# T_STorM32_motor_v25E.net
KiCad netlist of a schematic drawn in EAGLE
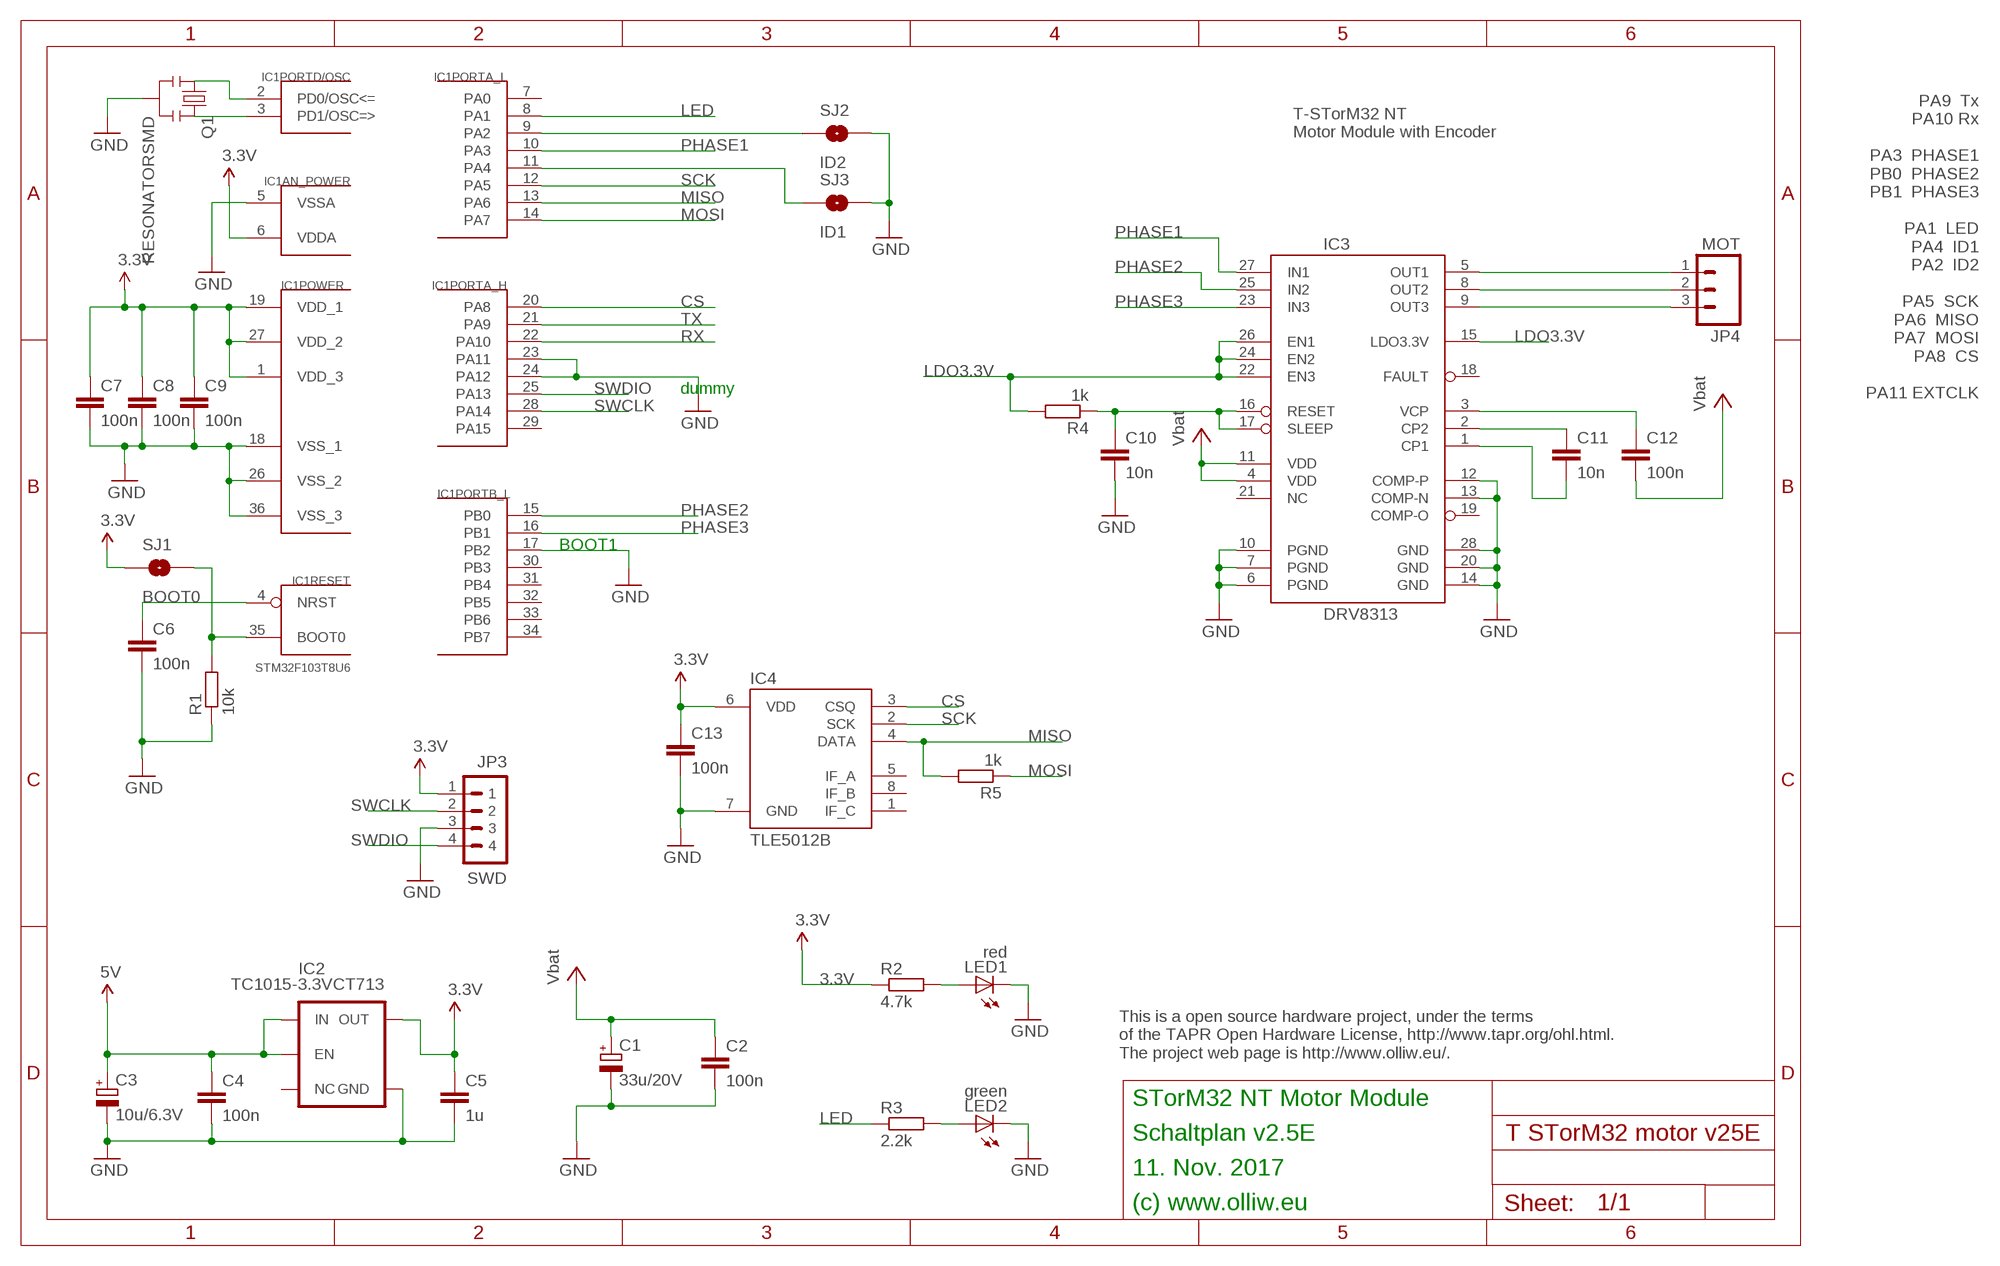
[diagram p0: schematic, sheet 1]

(export (version "E")
  (design (tool "Eeschema 10.0.6"))
  (components
    (comp (ref "C1")
      (value "33u/20V")
      (footprint "eagle-import:SMC_C")
      (libsource (lib "eagle-import") (part "CPOL-EUSMCC"))
    )
    (comp (ref "C2")
      (value "100n")
      (footprint "eagle-import:C0603")
      (libsource (lib "eagle-import") (part "C-EUC0603"))
    )
    (comp (ref "C3")
      (value "10u/6.3V")
      (footprint "eagle-import:SMC_B")
      (libsource (lib "eagle-import") (part "CPOL-EUSMCB"))
    )
    (comp (ref "C4")
      (value "100n")
      (footprint "eagle-import:C0603")
      (libsource (lib "eagle-import") (part "C-EUC0603"))
    )
    (comp (ref "C5")
      (value "1u")
      (footprint "eagle-import:C0603")
      (libsource (lib "eagle-import") (part "C-EUC0603"))
    )
    (comp (ref "C6")
      (value "100n")
      (footprint "eagle-import:C0603")
      (libsource (lib "eagle-import") (part "C-EUC0603"))
    )
    (comp (ref "C7")
      (value "100n")
      (footprint "eagle-import:C0603")
      (libsource (lib "eagle-import") (part "C-EUC0603"))
    )
    (comp (ref "C8")
      (value "100n")
      (footprint "eagle-import:C0603")
      (libsource (lib "eagle-import") (part "C-EUC0603"))
    )
    (comp (ref "C9")
      (value "100n")
      (footprint "eagle-import:C0603")
      (libsource (lib "eagle-import") (part "C-EUC0603"))
    )
    (comp (ref "C10")
      (value "10n")
      (footprint "eagle-import:C0603")
      (libsource (lib "eagle-import") (part "C-EUC0603"))
    )
    (comp (ref "C11")
      (value "10n")
      (footprint "eagle-import:C0603")
      (libsource (lib "eagle-import") (part "C-EUC0603"))
    )
    (comp (ref "C12")
      (value "100n")
      (footprint "eagle-import:C0603")
      (libsource (lib "eagle-import") (part "C-EUC0603"))
    )
    (comp (ref "C13")
      (value "100n")
      (footprint "eagle-import:C0603")
      (libsource (lib "eagle-import") (part "C-EUC0603"))
    )
    (comp (ref "IC1")
      (value "STM32F103T8U6")
      (footprint "eagle-import:VFQFPN36")
      (libsource (lib "eagle-import") (part "STM32F10XTXU6"))
    )
    (comp (ref "IC2")
      (value "TC1015-3.3VCT713")
      (footprint "eagle-import:SOT23-5")
      (libsource (lib "eagle-import") (part "V_REG_TPS76433SOT23-5"))
    )
    (comp (ref "IC3")
      (value "DRV8313")
      (footprint "eagle-import:HTSSOP28")
      (libsource (lib "eagle-import") (part "DRV8313"))
    )
    (comp (ref "IC4")
      (value "TLE5012B")
      (footprint "eagle-import:SO08")
      (libsource (lib "eagle-import") (part "TLE5012B"))
    )
    (comp (ref "JP3")
      (value "SWD")
      (footprint "eagle-import:4X1_1P27_OCT_BILEX")
      (libsource (lib "eagle-import") (part "P4X1_1P27-OCT_BILEX"))
    )
    (comp (ref "JP4")
      (value "MOT")
      (footprint "eagle-import:1X03_NO_SILK")
      (libsource (lib "eagle-import") (part "M031X03_NO_SILK"))
    )
    (comp (ref "LED1")
      (value "red")
      (footprint "eagle-import:CHIPLED_0603")
      (libsource (lib "eagle-import") (part "LEDCHIPLED_0603"))
    )
    (comp (ref "LED2")
      (value "green")
      (footprint "eagle-import:CHIPLED_0603")
      (libsource (lib "eagle-import") (part "LEDCHIPLED_0603"))
    )
    (comp (ref "Q1")
      (value "RESONATORSMD")
      (footprint "eagle-import:RESONATOR-SMD")
      (libsource (lib "eagle-import") (part "RESONATORSMD"))
    )
    (comp (ref "R1")
      (value "10k")
      (footprint "eagle-import:R0603")
      (libsource (lib "eagle-import") (part "R-EU_R0603"))
    )
    (comp (ref "R2")
      (value "4.7k")
      (footprint "eagle-import:R0603")
      (libsource (lib "eagle-import") (part "R-EU_R0603"))
    )
    (comp (ref "R3")
      (value "2.2k")
      (footprint "eagle-import:R0603")
      (libsource (lib "eagle-import") (part "R-EU_R0603"))
    )
    (comp (ref "R4")
      (value "1k")
      (footprint "eagle-import:R0603")
      (libsource (lib "eagle-import") (part "R-EU_R0603"))
    )
    (comp (ref "R5")
      (value "1k")
      (footprint "eagle-import:R0603")
      (libsource (lib "eagle-import") (part "R-EU_R0603"))
    )
    (comp (ref "SJ1")
      (value "BOOT0")
      (footprint "eagle-import:SJ_2S-NO")
      (libsource (lib "eagle-import") (part "SOLDERJUMPERNO"))
    )
    (comp (ref "SJ2")
      (value "ID2")
      (footprint "eagle-import:SJ_2S-NO")
      (libsource (lib "eagle-import") (part "SOLDERJUMPERNO"))
    )
    (comp (ref "SJ3")
      (value "ID1")
      (footprint "eagle-import:SJ_2S-NO")
      (libsource (lib "eagle-import") (part "SOLDERJUMPERNO"))
    )
  )
  (nets
    (net (code "1") (name "/CS") (class "Default")
      (node (ref "IC1") (pin "20") (pinfunction "PA8_20") (pintype "bidirectional"))
      (node (ref "IC4") (pin "3") (pinfunction "CSQ_3") (pintype "input"))
    )
    (net (code "2") (name "/LDO3.3V") (class "Default")
      (node (ref "IC3") (pin "15") (pinfunction "LDO3.3V_15") (pintype "output"))
      (node (ref "IC3") (pin "22") (pinfunction "EN3_22") (pintype "input"))
      (node (ref "IC3") (pin "24") (pinfunction "EN2_24") (pintype "input"))
      (node (ref "IC3") (pin "26") (pinfunction "EN1_26") (pintype "input"))
      (node (ref "R4") (pin "2") (pinfunction "2_2") (pintype "passive"))
    )
    (net (code "3") (name "/LED") (class "Default")
      (node (ref "IC1") (pin "8") (pinfunction "PA1_8") (pintype "bidirectional"))
      (node (ref "R3") (pin "1") (pinfunction "1_1") (pintype "passive"))
    )
    (net (code "4") (name "/MISO") (class "Default")
      (node (ref "IC1") (pin "13") (pinfunction "PA6_13") (pintype "bidirectional"))
      (node (ref "IC4") (pin "4") (pinfunction "DATA_4") (pintype "bidirectional"))
      (node (ref "R5") (pin "2") (pinfunction "2_2") (pintype "passive"))
    )
    (net (code "5") (name "/MOSI") (class "Default")
      (node (ref "IC1") (pin "14") (pinfunction "PA7_14") (pintype "bidirectional"))
      (node (ref "R5") (pin "1") (pinfunction "1_1") (pintype "passive"))
    )
    (net (code "6") (name "/PHASE1") (class "Default")
      (node (ref "IC1") (pin "10") (pinfunction "PA3_10") (pintype "bidirectional"))
      (node (ref "IC3") (pin "27") (pinfunction "IN1_27") (pintype "input"))
    )
    (net (code "7") (name "/PHASE2") (class "Default")
      (node (ref "IC1") (pin "15") (pinfunction "PB0_15") (pintype "bidirectional"))
      (node (ref "IC3") (pin "25") (pinfunction "IN2_25") (pintype "input"))
    )
    (net (code "8") (name "/PHASE3") (class "Default")
      (node (ref "IC1") (pin "16") (pinfunction "PB1_16") (pintype "bidirectional"))
      (node (ref "IC3") (pin "23") (pinfunction "IN3_23") (pintype "input"))
    )
    (net (code "9") (name "/RX") (class "Default")
      (node (ref "IC1") (pin "22") (pinfunction "PA10_22") (pintype "bidirectional"))
    )
    (net (code "10") (name "/SCK") (class "Default")
      (node (ref "IC1") (pin "12") (pinfunction "PA5_12") (pintype "bidirectional"))
      (node (ref "IC4") (pin "2") (pinfunction "SCK_2") (pintype "input"))
    )
    (net (code "11") (name "/SWCLK") (class "Default")
      (node (ref "IC1") (pin "28") (pinfunction "PA14_28") (pintype "bidirectional"))
      (node (ref "JP3") (pin "2") (pinfunction "2_2") (pintype "passive"))
    )
    (net (code "12") (name "/SWDIO") (class "Default")
      (node (ref "IC1") (pin "25") (pinfunction "PA13_25") (pintype "bidirectional"))
      (node (ref "JP3") (pin "4") (pinfunction "4_4") (pintype "passive"))
    )
    (net (code "13") (name "/TX") (class "Default")
      (node (ref "IC1") (pin "21") (pinfunction "PA9_21") (pintype "bidirectional"))
    )
    (net (code "14") (name "3.3V") (class "Default")
      (node (ref "C13") (pin "1") (pinfunction "1_1") (pintype "passive"))
      (node (ref "C5") (pin "1") (pinfunction "1_1") (pintype "passive"))
      (node (ref "C7") (pin "1") (pinfunction "1_1") (pintype "passive"))
      (node (ref "C8") (pin "1") (pinfunction "1_1") (pintype "passive"))
      (node (ref "C9") (pin "1") (pinfunction "1_1") (pintype "passive"))
      (node (ref "IC1") (pin "1") (pinfunction "VDD_3_1") (pintype "power_in"))
      (node (ref "IC1") (pin "19") (pinfunction "VDD_1_19") (pintype "power_in"))
      (node (ref "IC1") (pin "27") (pinfunction "VDD_2_27") (pintype "power_in"))
      (node (ref "IC1") (pin "6") (pinfunction "VDDA_6") (pintype "power_in"))
      (node (ref "IC2") (pin "5") (pinfunction "OUT_5") (pintype "passive"))
      (node (ref "IC4") (pin "6") (pinfunction "VDD_6") (pintype "power_in"))
      (node (ref "JP3") (pin "1") (pinfunction "1_1") (pintype "passive"))
      (node (ref "R2") (pin "1") (pinfunction "1_1") (pintype "passive"))
      (node (ref "SJ1") (pin "1") (pinfunction "1_1") (pintype "passive"))
    )
    (net (code "15") (name "5V") (class "Default")
      (node (ref "C3") (pin "+") (pinfunction "+_+") (pintype "passive"))
      (node (ref "C4") (pin "1") (pinfunction "1_1") (pintype "passive"))
      (node (ref "IC2") (pin "1") (pinfunction "IN_1") (pintype "input"))
      (node (ref "IC2") (pin "3") (pinfunction "EN_3") (pintype "input"))
    )
    (net (code "16") (name "GND") (class "Default")
      (node (ref "C1") (pin "-") (pinfunction "-_-") (pintype "passive"))
      (node (ref "C10") (pin "2") (pinfunction "2_2") (pintype "passive"))
      (node (ref "C13") (pin "2") (pinfunction "2_2") (pintype "passive"))
      (node (ref "C2") (pin "2") (pinfunction "2_2") (pintype "passive"))
      (node (ref "C3") (pin "-") (pinfunction "-_-") (pintype "passive"))
      (node (ref "C4") (pin "2") (pinfunction "2_2") (pintype "passive"))
      (node (ref "C5") (pin "2") (pinfunction "2_2") (pintype "passive"))
      (node (ref "C6") (pin "2") (pinfunction "2_2") (pintype "passive"))
      (node (ref "C7") (pin "2") (pinfunction "2_2") (pintype "passive"))
      (node (ref "C8") (pin "2") (pinfunction "2_2") (pintype "passive"))
      (node (ref "C9") (pin "2") (pinfunction "2_2") (pintype "passive"))
      (node (ref "IC1") (pin "17") (pinfunction "PB2_17") (pintype "bidirectional"))
      (node (ref "IC1") (pin "18") (pinfunction "VSS_1_18") (pintype "power_in"))
      (node (ref "IC1") (pin "23") (pinfunction "PA11_23") (pintype "bidirectional"))
      (node (ref "IC1") (pin "24") (pinfunction "PA12_24") (pintype "bidirectional"))
      (node (ref "IC1") (pin "26") (pinfunction "VSS_2_26") (pintype "power_in"))
      (node (ref "IC1") (pin "36") (pinfunction "VSS_3_36") (pintype "power_in"))
      (node (ref "IC1") (pin "5") (pinfunction "VSSA_5") (pintype "power_in"))
      (node (ref "IC2") (pin "2") (pinfunction "GND_2") (pintype "input"))
      (node (ref "IC3") (pin "10") (pinfunction "PGND_10") (pintype "power_in"))
      (node (ref "IC3") (pin "12") (pinfunction "COMP-P_12") (pintype "input"))
      (node (ref "IC3") (pin "13") (pinfunction "COMP-N_13") (pintype "input"))
      (node (ref "IC3") (pin "14") (pinfunction "GND_14") (pintype "power_in"))
      (node (ref "IC3") (pin "20") (pinfunction "GND_20") (pintype "power_in"))
      (node (ref "IC3") (pin "28") (pinfunction "GND_28") (pintype "power_in"))
      (node (ref "IC3") (pin "6") (pinfunction "PGND_6") (pintype "power_in"))
      (node (ref "IC3") (pin "7") (pinfunction "PGND_7") (pintype "power_in"))
      (node (ref "IC4") (pin "7") (pinfunction "GND_7") (pintype "power_in"))
      (node (ref "JP3") (pin "3") (pinfunction "3_3") (pintype "passive"))
      (node (ref "LED1") (pin "C") (pinfunction "C_C") (pintype "passive"))
      (node (ref "LED2") (pin "C") (pinfunction "C_C") (pintype "passive"))
      (node (ref "Q1") (pin "2") (pinfunction "2_2") (pintype "passive"))
      (node (ref "R1") (pin "1") (pinfunction "1_1") (pintype "passive"))
      (node (ref "SJ2") (pin "2") (pinfunction "2_2") (pintype "passive"))
      (node (ref "SJ3") (pin "2") (pinfunction "2_2") (pintype "passive"))
    )
    (net (code "17") (name "Net-(IC1C-PA2)") (class "Default")
      (node (ref "IC1") (pin "9") (pinfunction "PA2_9") (pintype "bidirectional"))
      (node (ref "SJ2") (pin "1") (pinfunction "1_1") (pintype "passive"))
    )
    (net (code "18") (name "Net-(IC1C-PA4)") (class "Default")
      (node (ref "IC1") (pin "11") (pinfunction "PA4_11") (pintype "bidirectional"))
      (node (ref "SJ3") (pin "1") (pinfunction "1_1") (pintype "passive"))
    )
    (net (code "19") (name "Net-(IC1E-PD0{slash}OSC<=)") (class "Default")
      (node (ref "IC1") (pin "2") (pinfunction "PD0/OSC<=_2") (pintype "bidirectional"))
      (node (ref "Q1") (pin "1") (pinfunction "1_1") (pintype "passive"))
    )
    (net (code "20") (name "Net-(IC1E-PD1{slash}OSC=>)") (class "Default")
      (node (ref "IC1") (pin "3") (pinfunction "PD1/OSC=>_3") (pintype "bidirectional"))
      (node (ref "Q1") (pin "3") (pinfunction "3_3") (pintype "passive"))
    )
    (net (code "21") (name "Net-(IC1G-BOOT0)") (class "Default")
      (node (ref "IC1") (pin "35") (pinfunction "BOOT0_35") (pintype "input"))
      (node (ref "R1") (pin "2") (pinfunction "2_2") (pintype "passive"))
      (node (ref "SJ1") (pin "2") (pinfunction "2_2") (pintype "passive"))
    )
    (net (code "22") (name "Net-(IC1G-NRST)") (class "Default")
      (node (ref "C6") (pin "1") (pinfunction "1_1") (pintype "passive"))
      (node (ref "IC1") (pin "4") (pinfunction "NRST_4") (pintype "input"))
    )
    (net (code "23") (name "Net-(IC3-CP1)") (class "Default")
      (node (ref "C11") (pin "2") (pinfunction "2_2") (pintype "passive"))
      (node (ref "IC3") (pin "1") (pinfunction "CP1_1") (pintype "bidirectional"))
    )
    (net (code "24") (name "Net-(IC3-CP2)") (class "Default")
      (node (ref "C11") (pin "1") (pinfunction "1_1") (pintype "passive"))
      (node (ref "IC3") (pin "2") (pinfunction "CP2_2") (pintype "bidirectional"))
    )
    (net (code "25") (name "Net-(IC3-OUT1)") (class "Default")
      (node (ref "IC3") (pin "5") (pinfunction "OUT1_5") (pintype "output"))
      (node (ref "JP4") (pin "1") (pinfunction "1_1") (pintype "passive"))
    )
    (net (code "26") (name "Net-(IC3-OUT2)") (class "Default")
      (node (ref "IC3") (pin "8") (pinfunction "OUT2_8") (pintype "output"))
      (node (ref "JP4") (pin "2") (pinfunction "2_2") (pintype "passive"))
    )
    (net (code "27") (name "Net-(IC3-OUT3)") (class "Default")
      (node (ref "IC3") (pin "9") (pinfunction "OUT3_9") (pintype "output"))
      (node (ref "JP4") (pin "3") (pinfunction "3_3") (pintype "passive"))
    )
    (net (code "28") (name "Net-(IC3-RESET)") (class "Default")
      (node (ref "C10") (pin "1") (pinfunction "1_1") (pintype "passive"))
      (node (ref "IC3") (pin "16") (pinfunction "RESET_16") (pintype "input"))
      (node (ref "IC3") (pin "17") (pinfunction "SLEEP_17") (pintype "input"))
      (node (ref "R4") (pin "1") (pinfunction "1_1") (pintype "passive"))
    )
    (net (code "29") (name "Net-(IC3-VCP)") (class "Default")
      (node (ref "C12") (pin "1") (pinfunction "1_1") (pintype "passive"))
      (node (ref "IC3") (pin "3") (pinfunction "VCP_3") (pintype "bidirectional"))
    )
    (net (code "30") (name "Net-(LED1-PadA)") (class "Default")
      (node (ref "LED1") (pin "A") (pinfunction "A_A") (pintype "passive"))
      (node (ref "R2") (pin "2") (pinfunction "2_2") (pintype "passive"))
    )
    (net (code "31") (name "Net-(LED2-PadA)") (class "Default")
      (node (ref "LED2") (pin "A") (pinfunction "A_A") (pintype "passive"))
      (node (ref "R3") (pin "2") (pinfunction "2_2") (pintype "passive"))
    )
    (net (code "32") (name "Vbat") (class "Default")
      (node (ref "C1") (pin "+") (pinfunction "+_+") (pintype "passive"))
      (node (ref "C12") (pin "2") (pinfunction "2_2") (pintype "passive"))
      (node (ref "C2") (pin "1") (pinfunction "1_1") (pintype "passive"))
      (node (ref "IC3") (pin "11") (pinfunction "VDD_11") (pintype "power_in"))
      (node (ref "IC3") (pin "4") (pinfunction "VDD_4") (pintype "power_in"))
    )
    (net (code "33") (name "unconnected-(IC1B-PA15-Pad29)") (class "Default")
      (node (ref "IC1") (pin "29") (pinfunction "PA15_29") (pintype "bidirectional"))
    )
    (net (code "34") (name "unconnected-(IC1C-PA0-Pad7)") (class "Default")
      (node (ref "IC1") (pin "7") (pinfunction "PA0_7") (pintype "bidirectional"))
    )
    (net (code "35") (name "unconnected-(IC1D-PB3-Pad30)") (class "Default")
      (node (ref "IC1") (pin "30") (pinfunction "PB3_30") (pintype "bidirectional"))
    )
    (net (code "36") (name "unconnected-(IC1D-PB4-Pad31)") (class "Default")
      (node (ref "IC1") (pin "31") (pinfunction "PB4_31") (pintype "bidirectional"))
    )
    (net (code "37") (name "unconnected-(IC1D-PB5-Pad32)") (class "Default")
      (node (ref "IC1") (pin "32") (pinfunction "PB5_32") (pintype "bidirectional"))
    )
    (net (code "38") (name "unconnected-(IC1D-PB6-Pad33)") (class "Default")
      (node (ref "IC1") (pin "33") (pinfunction "PB6_33") (pintype "bidirectional"))
    )
    (net (code "39") (name "unconnected-(IC1D-PB7-Pad34)") (class "Default")
      (node (ref "IC1") (pin "34") (pinfunction "PB7_34") (pintype "bidirectional"))
    )
    (net (code "40") (name "unconnected-(IC2-NC-Pad4)") (class "Default")
      (node (ref "IC2") (pin "4") (pinfunction "NC_4") (pintype "input"))
    )
    (net (code "41") (name "unconnected-(IC3-COMP-O-Pad19)") (class "Default")
      (node (ref "IC3") (pin "19") (pinfunction "COMP-O_19") (pintype "output"))
    )
    (net (code "42") (name "unconnected-(IC3-FAULT-Pad18)") (class "Default")
      (node (ref "IC3") (pin "18") (pinfunction "FAULT_18") (pintype "output"))
    )
    (net (code "43") (name "unconnected-(IC3-NC-Pad21)") (class "Default")
      (node (ref "IC3") (pin "21") (pinfunction "NC_21") (pintype "no_connect"))
    )
    (net (code "44") (name "unconnected-(IC4-IF_A-Pad5)") (class "Default")
      (node (ref "IC4") (pin "5") (pinfunction "IF_A_5") (pintype "bidirectional"))
    )
    (net (code "45") (name "unconnected-(IC4-IF_B-Pad8)") (class "Default")
      (node (ref "IC4") (pin "8") (pinfunction "IF_B_8") (pintype "output"))
    )
    (net (code "46") (name "unconnected-(IC4-IF_C-Pad1)") (class "Default")
      (node (ref "IC4") (pin "1") (pinfunction "IF_C_1") (pintype "bidirectional"))
    )
  )
)
